# ioh.net
KiCad netlist of a schematic drawn in EAGLE
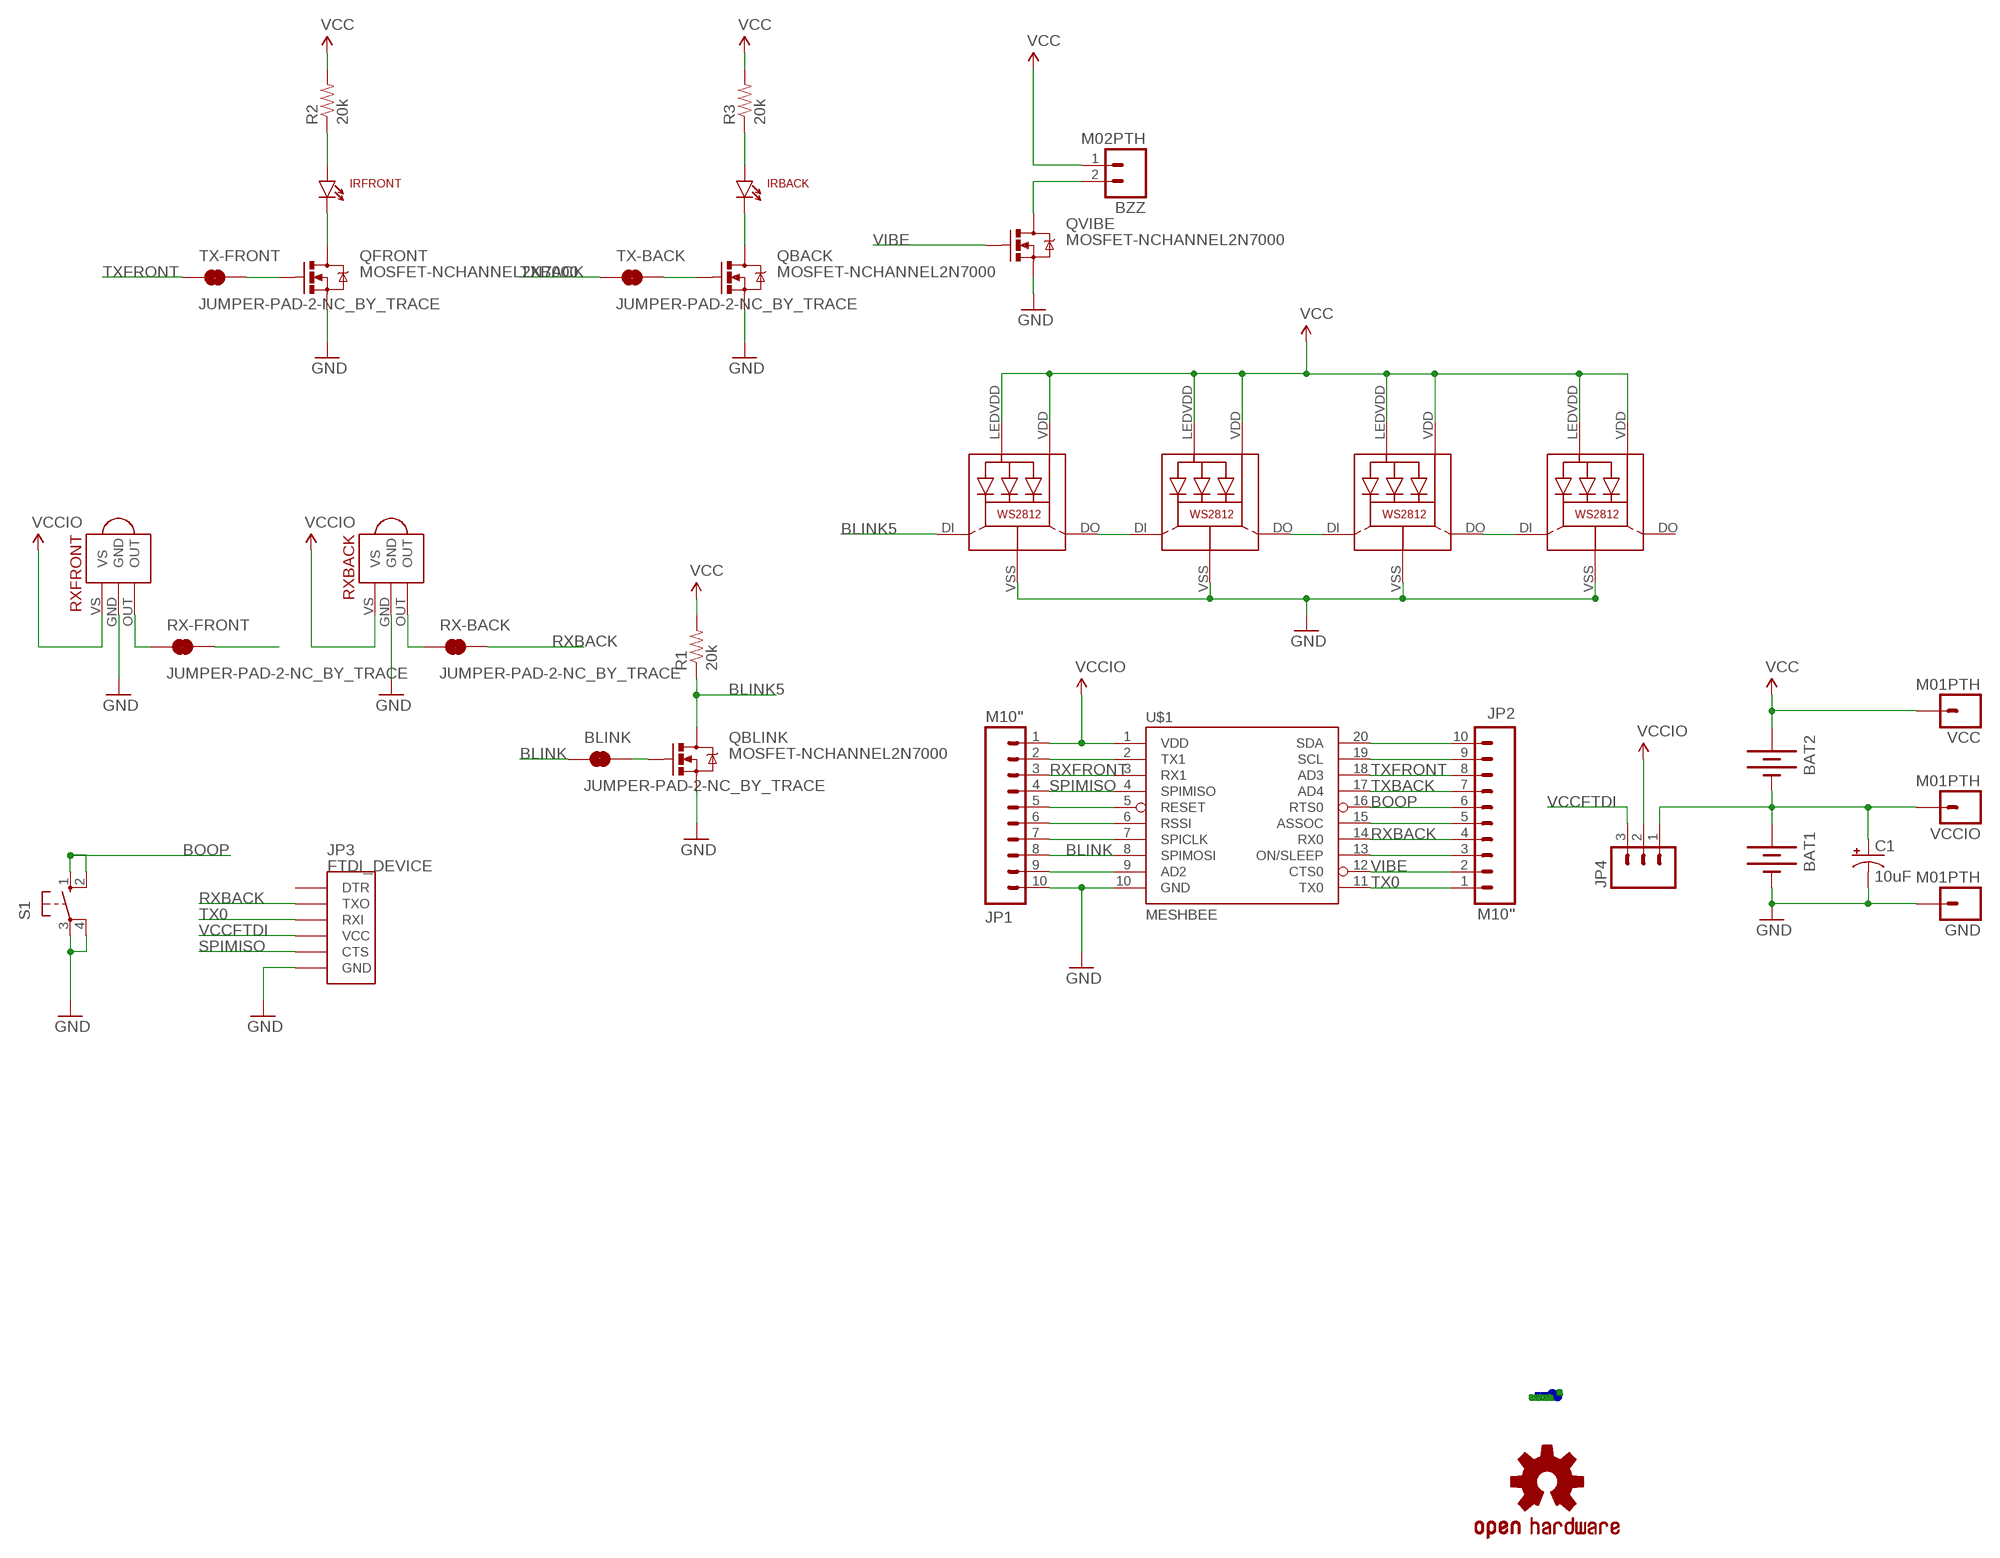
[diagram p0: schematic, sheet 1]

(export (version "E")
  (design (tool "Eeschema 10.0.6"))
  (components
    (comp (ref "BAT1")
      (value "BATTERY20PTH")
      (footprint "eagle-import:BATTCOM_20MM_PTH")
      (libsource (lib "eagle-import") (part "BATTERY20PTH"))
    )
    (comp (ref "BAT2")
      (value "BATTERY20PTH")
      (footprint "eagle-import:BATTCOM_20MM_PTH")
      (libsource (lib "eagle-import") (part "BATTERY20PTH"))
    )
    (comp (ref "BLINK")
      (value "JUMPER-PAD-2-NC_BY_TRACE")
      (footprint "eagle-import:PAD-JUMPER-2-NC_BY_TRACE_YES_SILK")
      (libsource (lib "eagle-import") (part "JUMPER-PAD-2-NC_BY_TRACE"))
    )
    (comp (ref "BZZ")
      (value "M02PTH")
      (footprint "eagle-import:1X02")
      (libsource (lib "eagle-import") (part "M02PTH"))
    )
    (comp (ref "C1")
      (value "10uF")
      (footprint "eagle-import:CPOL-RADIAL-10UF-25V-KIT")
      (libsource (lib "eagle-import") (part "10UF-25V-20%(PTH)KIT"))
    )
    (comp (ref "GND")
      (value "M01PTH")
      (footprint "eagle-import:1X01")
      (libsource (lib "eagle-import") (part "M01PTH"))
    )
    (comp (ref "IRBACK")
      (value "LTE-302")
      (footprint "eagle-import:LTE-302")
      (libsource (lib "eagle-import") (part "LTE-302"))
    )
    (comp (ref "IRFRONT")
      (value "LTE-302")
      (footprint "eagle-import:LTE-302")
      (libsource (lib "eagle-import") (part "LTE-302"))
    )
    (comp (ref "JP1")
      (value "M10\"")
      (footprint "eagle-import:1X10")
      (libsource (lib "eagle-import") (part "M10{dblquote}"))
    )
    (comp (ref "JP2")
      (value "M10\"")
      (footprint "eagle-import:1X10")
      (libsource (lib "eagle-import") (part "M10{dblquote}"))
    )
    (comp (ref "JP3")
      (value "FTDI_DEVICE")
      (footprint "eagle-import:FTDI_DEVICE_SIDE")
      (libsource (lib "eagle-import") (part "FTDI_DEVICE"))
    )
    (comp (ref "JP4")
      (value "M03LOCK")
      (footprint "eagle-import:1X03_LOCK")
      (libsource (lib "eagle-import") (part "M03LOCK"))
    )
    (comp (ref "LED2")
      (value "WS2812")
      (footprint "eagle-import:WS2812")
      (libsource (lib "eagle-import") (part "WS2812"))
    )
    (comp (ref "LED3")
      (value "WS2812")
      (footprint "eagle-import:WS2812")
      (libsource (lib "eagle-import") (part "WS2812"))
    )
    (comp (ref "LED4")
      (value "WS2812")
      (footprint "eagle-import:WS2812")
      (libsource (lib "eagle-import") (part "WS2812"))
    )
    (comp (ref "LED5")
      (value "WS2812")
      (footprint "eagle-import:WS2812")
      (libsource (lib "eagle-import") (part "WS2812"))
    )
    (comp (ref "LOGO1")
      (value "OSHW-LOGOS")
      (footprint "eagle-import:OSHW-LOGO-S")
      (libsource (lib "eagle-import") (part "OSHW-LOGOS"))
    )
    (comp (ref "QBACK")
      (value "MOSFET-NCHANNEL2N7000")
      (footprint "eagle-import:TO-92")
      (libsource (lib "eagle-import") (part "MOSFET-NCHANNEL2N7000"))
    )
    (comp (ref "QBLINK")
      (value "MOSFET-NCHANNEL2N7000")
      (footprint "eagle-import:TO-92")
      (libsource (lib "eagle-import") (part "MOSFET-NCHANNEL2N7000"))
    )
    (comp (ref "QFRONT")
      (value "MOSFET-NCHANNEL2N7000")
      (footprint "eagle-import:TO-92")
      (libsource (lib "eagle-import") (part "MOSFET-NCHANNEL2N7000"))
    )
    (comp (ref "QVIBE")
      (value "MOSFET-NCHANNEL2N7000")
      (footprint "eagle-import:TO-92")
      (libsource (lib "eagle-import") (part "MOSFET-NCHANNEL2N7000"))
    )
    (comp (ref "R1")
      (value "20k")
      (footprint "eagle-import:AXIAL-0.4")
      (libsource (lib "eagle-import") (part "RESISTORPTH-1/4W"))
    )
    (comp (ref "R2")
      (value "20k")
      (footprint "eagle-import:AXIAL-0.4")
      (libsource (lib "eagle-import") (part "RESISTORPTH-1/4W"))
    )
    (comp (ref "R3")
      (value "20k")
      (footprint "eagle-import:AXIAL-0.4")
      (libsource (lib "eagle-import") (part "RESISTORPTH-1/4W"))
    )
    (comp (ref "RX-BACK")
      (value "JUMPER-PAD-2-NC_BY_TRACE")
      (footprint "eagle-import:PAD-JUMPER-2-NC_BY_TRACE_YES_SILK")
      (libsource (lib "eagle-import") (part "JUMPER-PAD-2-NC_BY_TRACE"))
    )
    (comp (ref "RX-FRONT")
      (value "JUMPER-PAD-2-NC_BY_TRACE")
      (footprint "eagle-import:PAD-JUMPER-2-NC_BY_TRACE_YES_SILK")
      (libsource (lib "eagle-import") (part "JUMPER-PAD-2-NC_BY_TRACE"))
    )
    (comp (ref "RXBACK")
      (value "TSOP2438")
      (footprint "eagle-import:TSOP2438")
      (libsource (lib "eagle-import") (part "TSOP2438"))
    )
    (comp (ref "RXFRONT")
      (value "TSOP2438")
      (footprint "eagle-import:TSOP2438")
      (libsource (lib "eagle-import") (part "TSOP2438"))
    )
    (comp (ref "S1")
      (value "40-XX")
      (footprint "eagle-import:B3F-40XX")
      (fields (field (name "MF") "OMRON COMPONENTS USA") (field (name "MPN") "B3F-4000"))
      (libsource (lib "eagle-import") (part "40-XX"))
    )
    (comp (ref "TX-BACK")
      (value "JUMPER-PAD-2-NC_BY_TRACE")
      (footprint "eagle-import:PAD-JUMPER-2-NC_BY_TRACE_YES_SILK")
      (libsource (lib "eagle-import") (part "JUMPER-PAD-2-NC_BY_TRACE"))
    )
    (comp (ref "TX-FRONT")
      (value "JUMPER-PAD-2-NC_BY_TRACE")
      (footprint "eagle-import:PAD-JUMPER-2-NC_BY_TRACE_YES_SILK")
      (libsource (lib "eagle-import") (part "JUMPER-PAD-2-NC_BY_TRACE"))
    )
    (comp (ref "U$1")
      (value "MESHBEE")
      (footprint "eagle-import:MESHBEE")
      (libsource (lib "eagle-import") (part "MESHBEE"))
    )
    (comp (ref "U$2")
      (value "BSIDES")
      (footprint "eagle-import:BSIDES")
      (libsource (lib "eagle-import") (part "BSIDES"))
    )
    (comp (ref "VCC")
      (value "M01PTH")
      (footprint "eagle-import:1X01")
      (libsource (lib "eagle-import") (part "M01PTH"))
    )
    (comp (ref "VCCIO")
      (value "M01PTH")
      (footprint "eagle-import:1X01")
      (libsource (lib "eagle-import") (part "M01PTH"))
    )
  )
  (nets
    (net (code "1") (name "/BLINK") (class "Default")
      (node (ref "BLINK") (pin "1") (pinfunction "1_1") (pintype "passive"))
      (node (ref "JP1") (pin "8") (pinfunction "8_8") (pintype "passive"))
      (node (ref "U$1") (pin "8") (pinfunction "SPIMOSI_8") (pintype "bidirectional"))
    )
    (net (code "2") (name "/BLINK5") (class "Default")
      (node (ref "LED2") (pin "DI") (pinfunction "DI_DI") (pintype "input"))
      (node (ref "QBLINK") (pin "3") (pinfunction "D_3") (pintype "passive"))
      (node (ref "R1") (pin "P$1") (pinfunction "1_P$1") (pintype "passive"))
    )
    (net (code "3") (name "/BOOP") (class "Default")
      (node (ref "JP2") (pin "6") (pinfunction "6_6") (pintype "passive"))
      (node (ref "S1") (pin "1") (pinfunction "S_1") (pintype "passive"))
      (node (ref "S1") (pin "2") (pinfunction "S1_2") (pintype "passive"))
      (node (ref "U$1") (pin "16") (pinfunction "RTS0_16") (pintype "input"))
    )
    (net (code "4") (name "/RXBACK") (class "Default")
      (node (ref "JP2") (pin "4") (pinfunction "4_4") (pintype "passive"))
      (node (ref "JP3") (pin "P$2") (pinfunction "TXO_P$2") (pintype "bidirectional"))
      (node (ref "RX-BACK") (pin "2") (pinfunction "2_2") (pintype "passive"))
      (node (ref "U$1") (pin "14") (pinfunction "RX0_14") (pintype "bidirectional"))
    )
    (net (code "5") (name "/RXFRONT") (class "Default")
      (node (ref "JP1") (pin "3") (pinfunction "3_3") (pintype "passive"))
      (node (ref "RX-FRONT") (pin "2") (pinfunction "2_2") (pintype "passive"))
      (node (ref "U$1") (pin "3") (pinfunction "RX1_3") (pintype "input"))
    )
    (net (code "6") (name "/SPIMISO") (class "Default")
      (node (ref "JP1") (pin "4") (pinfunction "4_4") (pintype "passive"))
      (node (ref "JP3") (pin "P$5") (pinfunction "CTS_P$5") (pintype "bidirectional"))
      (node (ref "U$1") (pin "4") (pinfunction "SPIMISO_4") (pintype "bidirectional"))
    )
    (net (code "7") (name "/TX0") (class "Default")
      (node (ref "JP2") (pin "1") (pinfunction "1_1") (pintype "passive"))
      (node (ref "JP3") (pin "P$3") (pinfunction "RXI_P$3") (pintype "bidirectional"))
      (node (ref "U$1") (pin "11") (pinfunction "TX0_11") (pintype "bidirectional"))
    )
    (net (code "8") (name "/TXBACK") (class "Default")
      (node (ref "JP2") (pin "7") (pinfunction "7_7") (pintype "passive"))
      (node (ref "TX-BACK") (pin "1") (pinfunction "1_1") (pintype "passive"))
      (node (ref "U$1") (pin "17") (pinfunction "AD4_17") (pintype "bidirectional"))
    )
    (net (code "9") (name "/TXFRONT") (class "Default")
      (node (ref "JP2") (pin "8") (pinfunction "8_8") (pintype "passive"))
      (node (ref "TX-FRONT") (pin "1") (pinfunction "1_1") (pintype "passive"))
      (node (ref "U$1") (pin "18") (pinfunction "AD3_18") (pintype "bidirectional"))
    )
    (net (code "10") (name "/VCCFTDI") (class "Default")
      (node (ref "JP3") (pin "P$4") (pinfunction "VCC_P$4") (pintype "bidirectional"))
      (node (ref "JP4") (pin "3") (pinfunction "3_3") (pintype "passive"))
    )
    (net (code "11") (name "/VIBE") (class "Default")
      (node (ref "JP2") (pin "2") (pinfunction "2_2") (pintype "passive"))
      (node (ref "QVIBE") (pin "2") (pinfunction "G_2") (pintype "passive"))
      (node (ref "U$1") (pin "12") (pinfunction "CTS0_12") (pintype "output"))
    )
    (net (code "12") (name "GND") (class "Default")
      (node (ref "BAT1") (pin "2") (pinfunction "-_2") (pintype "power_in"))
      (node (ref "C1") (pin "2") (pinfunction "-_2") (pintype "passive"))
      (node (ref "GND") (pin "1") (pinfunction "1_1") (pintype "passive"))
      (node (ref "JP1") (pin "10") (pinfunction "10_10") (pintype "passive"))
      (node (ref "JP3") (pin "P$6") (pinfunction "GND_P$6") (pintype "bidirectional"))
      (node (ref "LED2") (pin "VSS") (pinfunction "GND_VSS") (pintype "power_in"))
      (node (ref "LED3") (pin "VSS") (pinfunction "GND_VSS") (pintype "power_in"))
      (node (ref "LED4") (pin "VSS") (pinfunction "GND_VSS") (pintype "power_in"))
      (node (ref "LED5") (pin "VSS") (pinfunction "GND_VSS") (pintype "power_in"))
      (node (ref "QBACK") (pin "1") (pinfunction "S_1") (pintype "passive"))
      (node (ref "QBLINK") (pin "1") (pinfunction "S_1") (pintype "passive"))
      (node (ref "QFRONT") (pin "1") (pinfunction "S_1") (pintype "passive"))
      (node (ref "QVIBE") (pin "1") (pinfunction "S_1") (pintype "passive"))
      (node (ref "RXBACK") (pin "GND") (pinfunction "GND_GND") (pintype "power_in"))
      (node (ref "RXFRONT") (pin "GND") (pinfunction "GND_GND") (pintype "power_in"))
      (node (ref "S1") (pin "3") (pinfunction "P_3") (pintype "passive"))
      (node (ref "S1") (pin "4") (pinfunction "P1_4") (pintype "passive"))
      (node (ref "U$1") (pin "10") (pinfunction "GND_10") (pintype "power_in"))
    )
    (net (code "13") (name "Net-(BAT1-+)") (class "Default")
      (node (ref "BAT1") (pin "1") (pinfunction "+_1") (pintype "power_in"))
      (node (ref "BAT2") (pin "2") (pinfunction "-_2") (pintype "power_in"))
      (node (ref "C1") (pin "1") (pinfunction "+_1") (pintype "passive"))
      (node (ref "JP4") (pin "1") (pinfunction "1_1") (pintype "passive"))
      (node (ref "VCCIO") (pin "1") (pinfunction "1_1") (pintype "passive"))
    )
    (net (code "14") (name "Net-(LED2-PadDO)") (class "Default")
      (node (ref "LED2") (pin "DO") (pinfunction "DO_DO") (pintype "output"))
      (node (ref "LED3") (pin "DI") (pinfunction "DI_DI") (pintype "input"))
    )
    (net (code "15") (name "Net-(LED3-PadDO)") (class "Default")
      (node (ref "LED3") (pin "DO") (pinfunction "DO_DO") (pintype "output"))
      (node (ref "LED4") (pin "DI") (pinfunction "DI_DI") (pintype "input"))
    )
    (net (code "16") (name "Net-(LED4-PadDO)") (class "Default")
      (node (ref "LED4") (pin "DO") (pinfunction "DO_DO") (pintype "output"))
      (node (ref "LED5") (pin "DI") (pinfunction "DI_DI") (pintype "input"))
    )
    (net (code "17") (name "Net-(QBACK-D)") (class "Default")
      (node (ref "IRBACK") (pin "C") (pinfunction "C_C") (pintype "bidirectional"))
      (node (ref "QBACK") (pin "3") (pinfunction "D_3") (pintype "passive"))
    )
    (net (code "18") (name "Net-(QBACK-G)") (class "Default")
      (node (ref "QBACK") (pin "2") (pinfunction "G_2") (pintype "passive"))
      (node (ref "TX-BACK") (pin "2") (pinfunction "2_2") (pintype "passive"))
    )
    (net (code "19") (name "Net-(QBLINK-G)") (class "Default")
      (node (ref "BLINK") (pin "2") (pinfunction "2_2") (pintype "passive"))
      (node (ref "QBLINK") (pin "2") (pinfunction "G_2") (pintype "passive"))
    )
    (net (code "20") (name "Net-(QFRONT-D)") (class "Default")
      (node (ref "IRFRONT") (pin "C") (pinfunction "C_C") (pintype "bidirectional"))
      (node (ref "QFRONT") (pin "3") (pinfunction "D_3") (pintype "passive"))
    )
    (net (code "21") (name "Net-(QFRONT-G)") (class "Default")
      (node (ref "QFRONT") (pin "2") (pinfunction "G_2") (pintype "passive"))
      (node (ref "TX-FRONT") (pin "2") (pinfunction "2_2") (pintype "passive"))
    )
    (net (code "22") (name "Net-(QVIBE-D)") (class "Default")
      (node (ref "BZZ") (pin "2") (pinfunction "2_2") (pintype "passive"))
      (node (ref "QVIBE") (pin "3") (pinfunction "D_3") (pintype "passive"))
    )
    (net (code "23") (name "Net-(R2-1)") (class "Default")
      (node (ref "IRFRONT") (pin "A") (pinfunction "A_A") (pintype "bidirectional"))
      (node (ref "R2") (pin "P$1") (pinfunction "1_P$1") (pintype "passive"))
    )
    (net (code "24") (name "Net-(R3-1)") (class "Default")
      (node (ref "IRBACK") (pin "A") (pinfunction "A_A") (pintype "bidirectional"))
      (node (ref "R3") (pin "P$1") (pinfunction "1_P$1") (pintype "passive"))
    )
    (net (code "25") (name "Net-(RX-BACK-Pad1)") (class "Default")
      (node (ref "RX-BACK") (pin "1") (pinfunction "1_1") (pintype "passive"))
      (node (ref "RXBACK") (pin "OUT") (pinfunction "OUT_OUT") (pintype "output"))
    )
    (net (code "26") (name "Net-(RX-FRONT-Pad1)") (class "Default")
      (node (ref "RX-FRONT") (pin "1") (pinfunction "1_1") (pintype "passive"))
      (node (ref "RXFRONT") (pin "OUT") (pinfunction "OUT_OUT") (pintype "output"))
    )
    (net (code "27") (name "Net-(U$1-AD2)") (class "Default")
      (node (ref "JP1") (pin "9") (pinfunction "9_9") (pintype "passive"))
      (node (ref "U$1") (pin "9") (pinfunction "AD2_9") (pintype "bidirectional"))
    )
    (net (code "28") (name "Net-(U$1-ASSOC)") (class "Default")
      (node (ref "JP2") (pin "5") (pinfunction "5_5") (pintype "passive"))
      (node (ref "U$1") (pin "15") (pinfunction "ASSOC_15") (pintype "bidirectional"))
    )
    (net (code "29") (name "Net-(U$1-ON{slash}SLEEP)") (class "Default")
      (node (ref "JP2") (pin "3") (pinfunction "3_3") (pintype "passive"))
      (node (ref "U$1") (pin "13") (pinfunction "ON/SLEEP_13") (pintype "bidirectional"))
    )
    (net (code "30") (name "Net-(U$1-RESET)") (class "Default")
      (node (ref "JP1") (pin "5") (pinfunction "5_5") (pintype "passive"))
      (node (ref "U$1") (pin "5") (pinfunction "RESET_5") (pintype "input"))
    )
    (net (code "31") (name "Net-(U$1-RSSI)") (class "Default")
      (node (ref "JP1") (pin "6") (pinfunction "6_6") (pintype "passive"))
      (node (ref "U$1") (pin "6") (pinfunction "RSSI_6") (pintype "bidirectional"))
    )
    (net (code "32") (name "Net-(U$1-SCL)") (class "Default")
      (node (ref "JP2") (pin "9") (pinfunction "9_9") (pintype "passive"))
      (node (ref "U$1") (pin "19") (pinfunction "SCL_19") (pintype "bidirectional"))
    )
    (net (code "33") (name "Net-(U$1-SDA)") (class "Default")
      (node (ref "JP2") (pin "10") (pinfunction "10_10") (pintype "passive"))
      (node (ref "U$1") (pin "20") (pinfunction "SDA_20") (pintype "bidirectional"))
    )
    (net (code "34") (name "Net-(U$1-SPICLK)") (class "Default")
      (node (ref "JP1") (pin "7") (pinfunction "7_7") (pintype "passive"))
      (node (ref "U$1") (pin "7") (pinfunction "SPICLK_7") (pintype "bidirectional"))
    )
    (net (code "35") (name "Net-(U$1-TX1)") (class "Default")
      (node (ref "JP1") (pin "2") (pinfunction "2_2") (pintype "passive"))
      (node (ref "U$1") (pin "2") (pinfunction "TX1_2") (pintype "output"))
    )
    (net (code "36") (name "VCC") (class "Default")
      (node (ref "BAT2") (pin "1") (pinfunction "+_1") (pintype "power_in"))
      (node (ref "BZZ") (pin "1") (pinfunction "1_1") (pintype "passive"))
      (node (ref "LED2") (pin "LEDVDD") (pinfunction "LEDVDD_LEDVDD") (pintype "power_in"))
      (node (ref "LED2") (pin "VDD") (pinfunction "VDD_VDD") (pintype "power_in"))
      (node (ref "LED3") (pin "LEDVDD") (pinfunction "LEDVDD_LEDVDD") (pintype "power_in"))
      (node (ref "LED3") (pin "VDD") (pinfunction "VDD_VDD") (pintype "power_in"))
      (node (ref "LED4") (pin "LEDVDD") (pinfunction "LEDVDD_LEDVDD") (pintype "power_in"))
      (node (ref "LED4") (pin "VDD") (pinfunction "VDD_VDD") (pintype "power_in"))
      (node (ref "LED5") (pin "LEDVDD") (pinfunction "LEDVDD_LEDVDD") (pintype "power_in"))
      (node (ref "LED5") (pin "VDD") (pinfunction "VDD_VDD") (pintype "power_in"))
      (node (ref "R1") (pin "P$2") (pinfunction "2_P$2") (pintype "passive"))
      (node (ref "R2") (pin "P$2") (pinfunction "2_P$2") (pintype "passive"))
      (node (ref "R3") (pin "P$2") (pinfunction "2_P$2") (pintype "passive"))
      (node (ref "VCC") (pin "1") (pinfunction "1_1") (pintype "passive"))
    )
    (net (code "37") (name "VCCIO") (class "Default")
      (node (ref "JP1") (pin "1") (pinfunction "1_1") (pintype "passive"))
      (node (ref "JP4") (pin "2") (pinfunction "2_2") (pintype "passive"))
      (node (ref "RXBACK") (pin "VS") (pinfunction "VS_VS") (pintype "power_in"))
      (node (ref "RXFRONT") (pin "VS") (pinfunction "VS_VS") (pintype "power_in"))
      (node (ref "U$1") (pin "1") (pinfunction "VDD_1") (pintype "power_in"))
    )
    (net (code "38") (name "unconnected-(JP3-DTR-PadP$1)") (class "Default")
      (node (ref "JP3") (pin "P$1") (pinfunction "DTR_P$1") (pintype "bidirectional"))
    )
    (net (code "39") (name "unconnected-(LED5-PadDO)") (class "Default")
      (node (ref "LED5") (pin "DO") (pinfunction "DO_DO") (pintype "output"))
    )
  )
)
